# BME280_Daughter_1_2.net
KiCad netlist of a schematic drawn in EAGLE
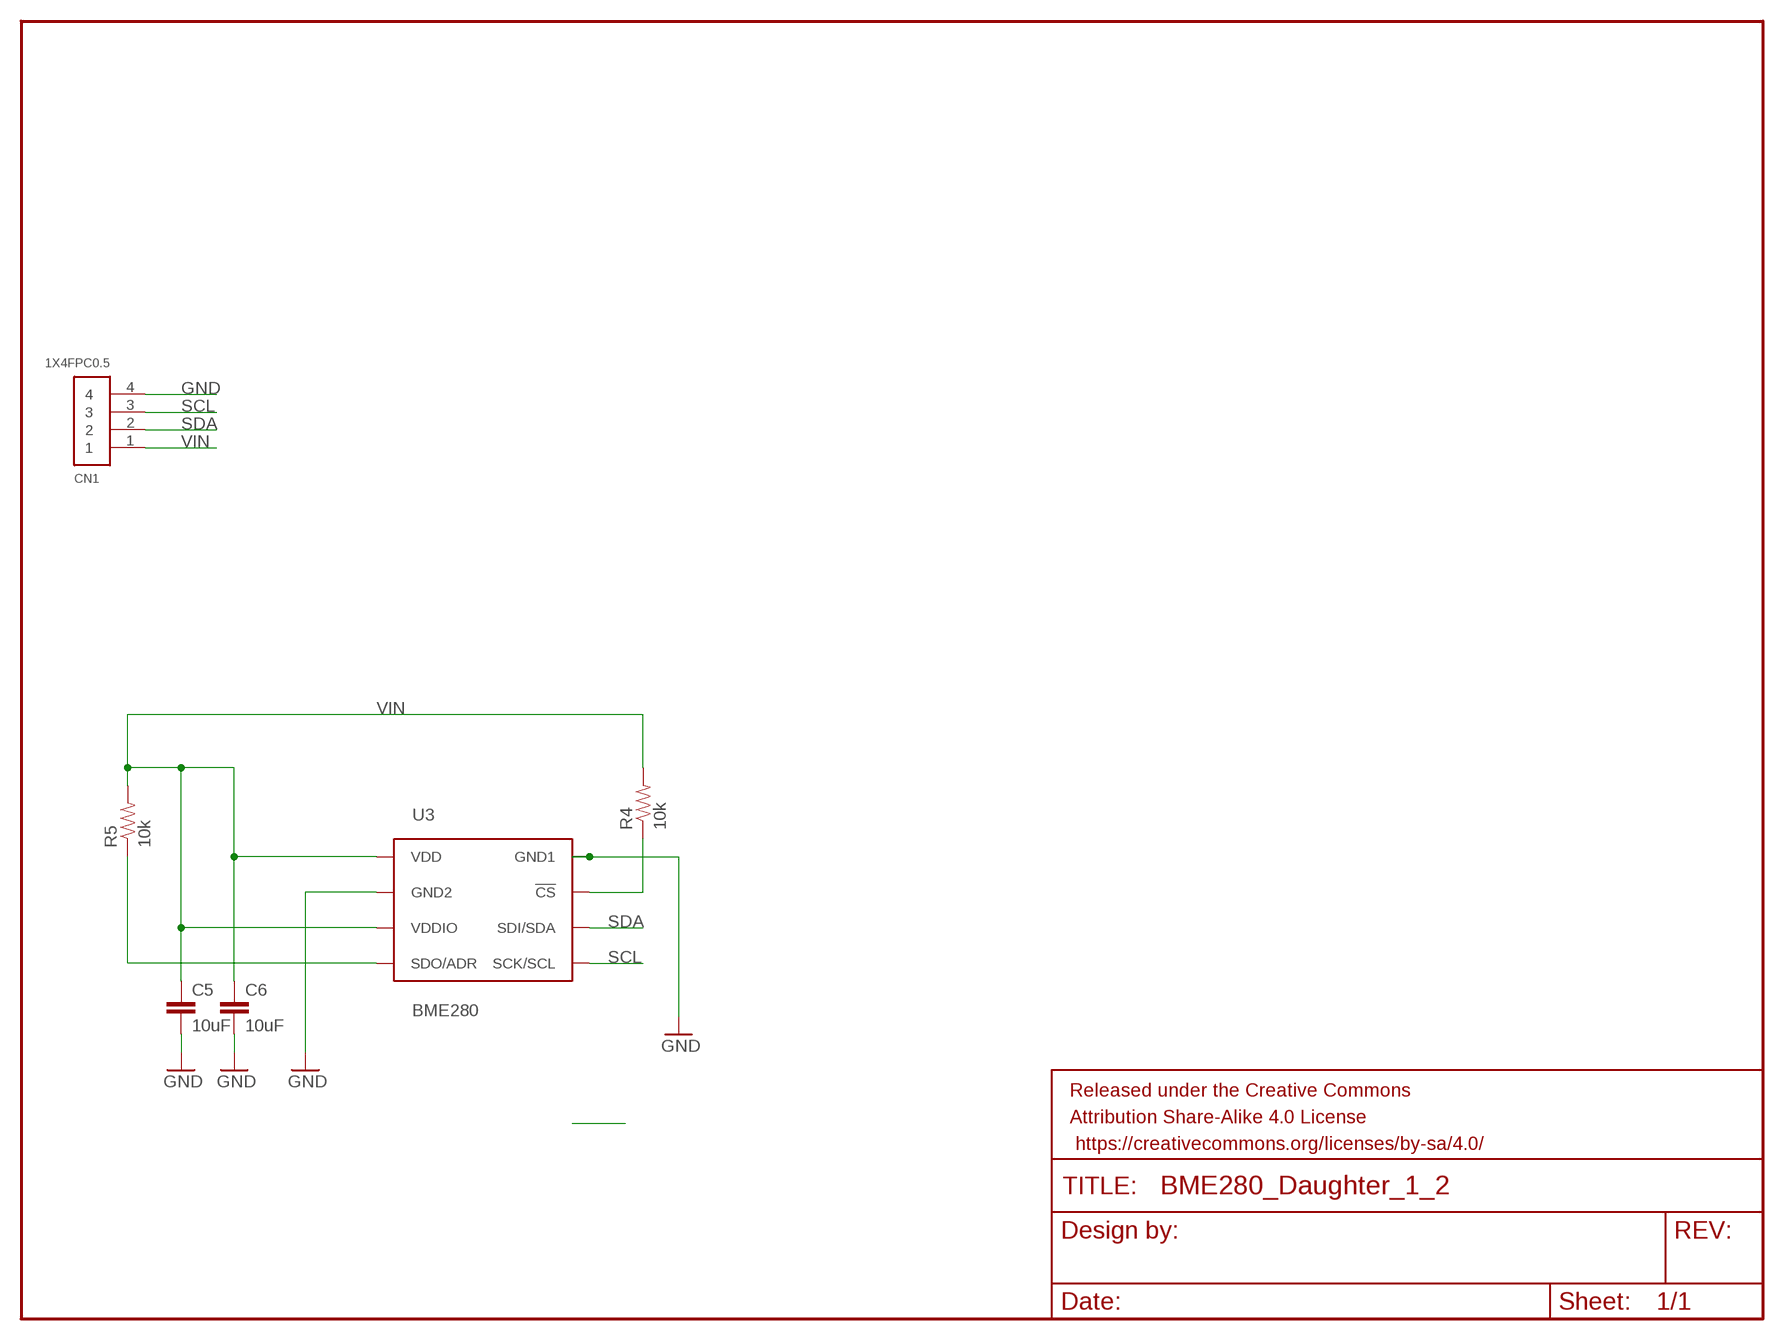
[diagram p0: schematic, sheet 1]

(export (version "E")
  (design (tool "Eeschema 10.0.6"))
  (components
    (comp (ref "C5")
      (value "10uF")
      (footprint "eagle-import:0805")
      (libsource (lib "eagle-import") (part "CAP0805"))
    )
    (comp (ref "C6")
      (value "10uF")
      (footprint "eagle-import:0805")
      (libsource (lib "eagle-import") (part "CAP0805"))
    )
    (comp (ref "CN1")
      (value "1X4FPC0.5")
      (footprint "eagle-import:FPC_0.5MM-4")
      (libsource (lib "eagle-import") (part "1X4FPC0.5"))
    )
    (comp (ref "FRAME1")
      (value "FRAME-LETTER")
      (footprint "eagle-import:CREATIVE_COMMONS")
      (libsource (lib "eagle-import") (part "FRAME-LETTER"))
    )
    (comp (ref "R4")
      (value "10k")
      (footprint "eagle-import:0805")
      (libsource (lib "eagle-import") (part "RESISTOR0805-RES"))
    )
    (comp (ref "R5")
      (value "10k")
      (footprint "eagle-import:0805")
      (libsource (lib "eagle-import") (part "RESISTOR0805-RES"))
    )
    (comp (ref "U3")
      (value "BME280")
      (footprint "eagle-import:BME280_LGA")
      (libsource (lib "eagle-import") (part "BME280"))
    )
  )
  (nets
    (net (code "1") (name "/SCL") (class "Default")
      (node (ref "CN1") (pin "3") (pinfunction "3_3") (pintype "bidirectional"))
      (node (ref "U3") (pin "P$4") (pinfunction "SCK/SCL_P$4") (pintype "bidirectional"))
    )
    (net (code "2") (name "/SDA") (class "Default")
      (node (ref "CN1") (pin "2") (pinfunction "2_2") (pintype "bidirectional"))
      (node (ref "U3") (pin "P$3") (pinfunction "SDI/SDA_P$3") (pintype "bidirectional"))
    )
    (net (code "3") (name "/VIN") (class "Default")
      (node (ref "C5") (pin "1") (pinfunction "1_1") (pintype "passive"))
      (node (ref "C6") (pin "1") (pinfunction "1_1") (pintype "passive"))
      (node (ref "CN1") (pin "1") (pinfunction "1_1") (pintype "bidirectional"))
      (node (ref "R4") (pin "2") (pinfunction "2_2") (pintype "passive"))
      (node (ref "R5") (pin "2") (pinfunction "2_2") (pintype "passive"))
      (node (ref "U3") (pin "P$6") (pinfunction "VDDIO_P$6") (pintype "bidirectional"))
      (node (ref "U3") (pin "P$8") (pinfunction "VDD_P$8") (pintype "bidirectional"))
    )
    (net (code "4") (name "GND") (class "Default")
      (node (ref "C5") (pin "2") (pinfunction "2_2") (pintype "passive"))
      (node (ref "C6") (pin "2") (pinfunction "2_2") (pintype "passive"))
      (node (ref "CN1") (pin "4") (pinfunction "4_4") (pintype "bidirectional"))
      (node (ref "U3") (pin "P$1") (pinfunction "GND1_P$1") (pintype "bidirectional"))
      (node (ref "U3") (pin "P$7") (pinfunction "GND2_P$7") (pintype "bidirectional"))
    )
    (net (code "5") (name "Net-(U3-SDO{slash}ADR)") (class "Default")
      (node (ref "R5") (pin "1") (pinfunction "1_1") (pintype "passive"))
      (node (ref "U3") (pin "P$5") (pinfunction "SDO/ADR_P$5") (pintype "bidirectional"))
    )
    (net (code "6") (name "Net-(U3-~{CS})") (class "Default")
      (node (ref "R4") (pin "1") (pinfunction "1_1") (pintype "passive"))
      (node (ref "U3") (pin "P$2") (pinfunction "~{CS}_P$2") (pintype "bidirectional"))
    )
  )
)
